# MCUDEV_TFT_144.net
KiCad netlist of a schematic drawn in Altium Designer
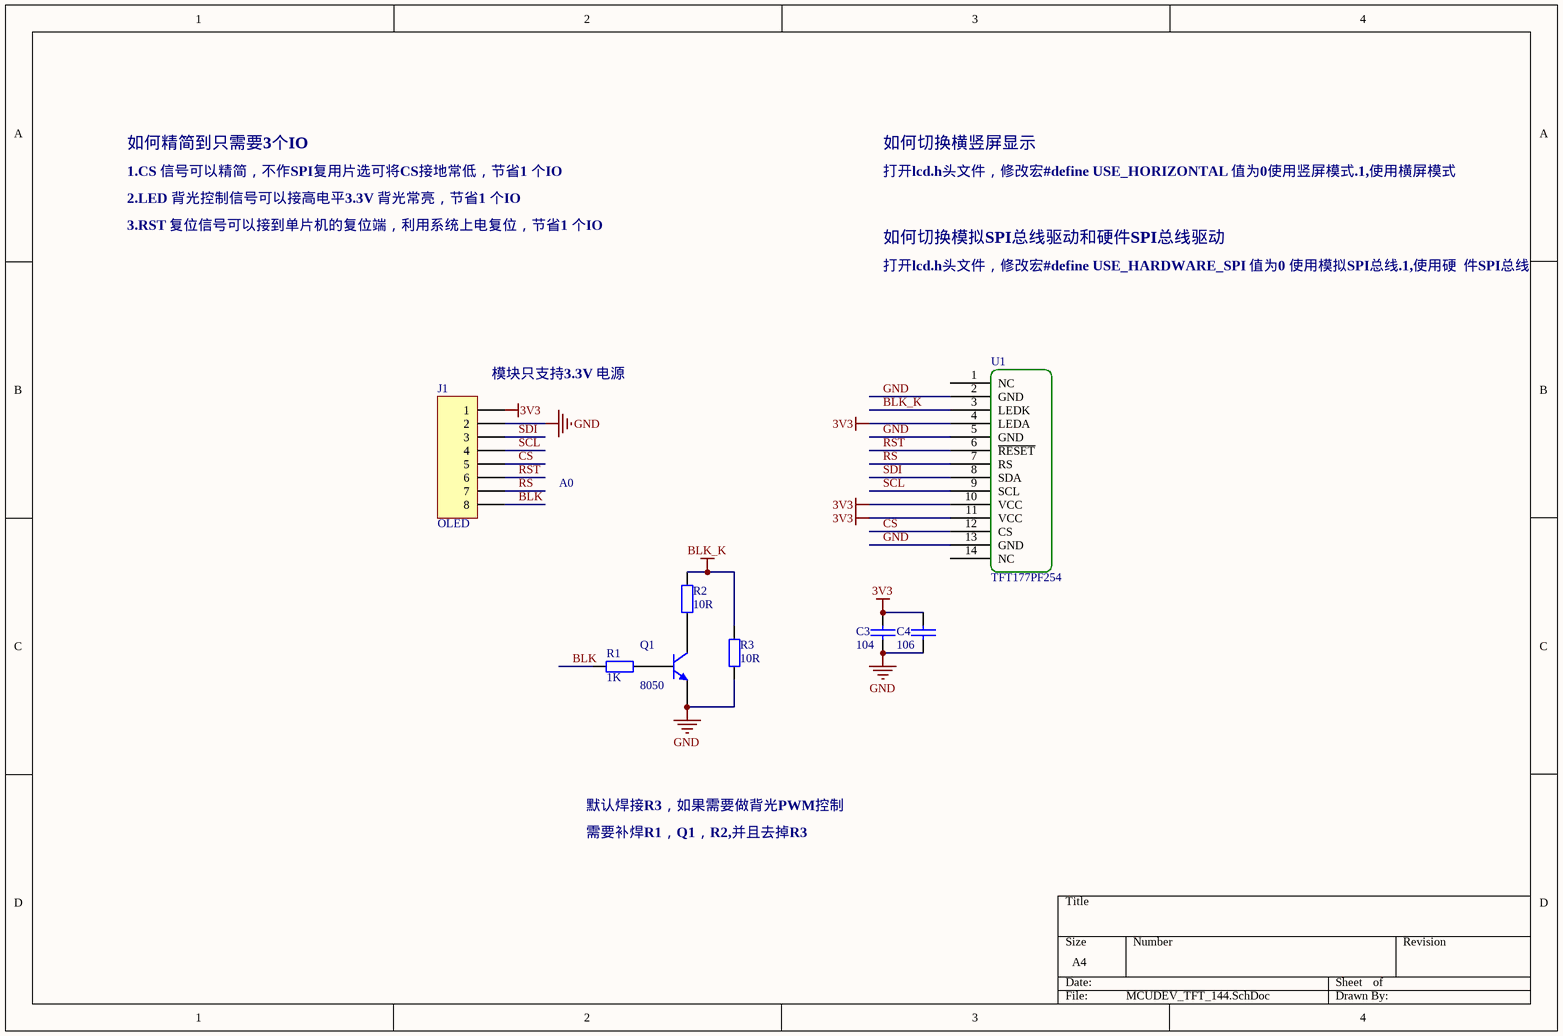
[diagram p0: MCUDEV_TFT_144.SchDoc]

(export (version "E")
  (design (tool "Eeschema 10.0.6"))
  (components
    (comp (ref "C3")
      (value "104")
      (footprint "RC0603")
      (description "Capacitor")
      (libsource (lib "*") (part "CAP"))
    )
    (comp (ref "C4")
      (value "106")
      (footprint "RC0805")
      (description "Capacitor")
      (libsource (lib "*") (part "CAP"))
    )
    (comp (ref "J1")
      (value "OLED")
      (footprint "LCD_SPI8")
      (description "Header, 8-Pin")
      (fields (field (name "PUBLISHER") "Altium Limited"))
      (libsource (lib "Miscellaneous Connectors") (part "Header 8"))
    )
    (comp (ref "Q1")
      (value "8050")
      (footprint "NPN")
      (description "NPN General Purpose Amplifier")
      (libsource (lib "Miscellaneous Devices") (part "2N3904"))
    )
    (comp (ref "R1")
      (value "1K")
      (footprint "RC0603")
      (description "Resistor")
      (libsource (lib "Miscellaneous Devices") (part "Res2"))
    )
    (comp (ref "R2")
      (value "10R")
      (footprint "RC0603")
      (description "Resistor")
      (libsource (lib "") (part "Res2_1"))
    )
    (comp (ref "R3")
      (value "10R")
      (footprint "RC0603")
      (description "Resistor")
      (libsource (lib "") (part "Res2_1"))
    )
    (comp (ref "U1")
      (value "TFT177PF254")
      (footprint "TFT177PF254")
      (libsource (lib "1.44寸串口液晶屏原理图封装_14Pin") (part "TFT177PF254"))
    )
  )
  (nets
    (net (code "1") (name "/BLK") (class "Default")
      (node (ref "J1") (pin "8") (pinfunction "8_8") (pintype "passive"))
      (node (ref "R1") (pin "2") (pinfunction "2_2") (pintype "passive"))
    )
    (net (code "2") (name "/CS") (class "Default")
      (node (ref "J1") (pin "5") (pinfunction "5_5") (pintype "passive"))
      (node (ref "U1") (pin "12") (pinfunction "CS_12") (pintype "passive"))
    )
    (net (code "3") (name "/RS") (class "Default")
      (node (ref "J1") (pin "7") (pinfunction "7_7") (pintype "passive"))
      (node (ref "U1") (pin "7") (pinfunction "RS_7") (pintype "passive"))
    )
    (net (code "4") (name "/RST") (class "Default")
      (node (ref "J1") (pin "6") (pinfunction "6_6") (pintype "passive"))
      (node (ref "U1") (pin "6") (pinfunction "~{RESET}_6") (pintype "passive"))
    )
    (net (code "5") (name "/SCL") (class "Default")
      (node (ref "J1") (pin "4") (pinfunction "4_4") (pintype "passive"))
      (node (ref "U1") (pin "9") (pinfunction "SCL_9") (pintype "passive"))
    )
    (net (code "6") (name "/SDI") (class "Default")
      (node (ref "J1") (pin "3") (pinfunction "3_3") (pintype "passive"))
      (node (ref "U1") (pin "8") (pinfunction "SDA_8") (pintype "passive"))
    )
    (net (code "7") (name "3V3") (class "Default")
      (node (ref "C3") (pin "1") (pinfunction "1_1") (pintype "passive"))
      (node (ref "C4") (pin "1") (pinfunction "1_1") (pintype "passive"))
      (node (ref "J1") (pin "1") (pinfunction "1_1") (pintype "passive"))
      (node (ref "U1") (pin "10") (pinfunction "VCC_10") (pintype "passive"))
      (node (ref "U1") (pin "11") (pinfunction "VCC_11") (pintype "passive"))
      (node (ref "U1") (pin "4") (pinfunction "LEDA_4") (pintype "passive"))
    )
    (net (code "8") (name "BLK_K") (class "Default")
      (node (ref "R2") (pin "2") (pinfunction "2_2") (pintype "passive"))
      (node (ref "R3") (pin "2") (pinfunction "2_2") (pintype "passive"))
      (node (ref "U1") (pin "3") (pinfunction "LEDK_3") (pintype "passive"))
    )
    (net (code "9") (name "GND") (class "Default")
      (node (ref "C3") (pin "2") (pinfunction "2_2") (pintype "passive"))
      (node (ref "C4") (pin "2") (pinfunction "2_2") (pintype "passive"))
      (node (ref "J1") (pin "2") (pinfunction "2_2") (pintype "passive"))
      (node (ref "Q1") (pin "3") (pinfunction "E_3") (pintype "passive"))
      (node (ref "R3") (pin "1") (pinfunction "1_1") (pintype "passive"))
      (node (ref "U1") (pin "13") (pinfunction "GND_13") (pintype "passive"))
      (node (ref "U1") (pin "2") (pinfunction "GND_2") (pintype "passive"))
      (node (ref "U1") (pin "5") (pinfunction "GND_5") (pintype "passive"))
    )
    (net (code "10") (name "Net-(Q1-B)") (class "Default")
      (node (ref "Q1") (pin "1") (pinfunction "B_1") (pintype "passive"))
      (node (ref "R1") (pin "1") (pinfunction "1_1") (pintype "passive"))
    )
    (net (code "11") (name "Net-(Q1-C)") (class "Default")
      (node (ref "Q1") (pin "2") (pinfunction "C_2") (pintype "passive"))
      (node (ref "R2") (pin "1") (pinfunction "1_1") (pintype "passive"))
    )
    (net (code "12") (name "unconnected-(U1-NC-Pad1)") (class "Default")
      (node (ref "U1") (pin "1") (pinfunction "NC_1") (pintype "passive"))
    )
    (net (code "13") (name "unconnected-(U1-NC-Pad14)") (class "Default")
      (node (ref "U1") (pin "14") (pinfunction "NC_14") (pintype "passive"))
    )
  )
)
